# XPanel.net
KiCad netlist of a schematic drawn in EAGLE
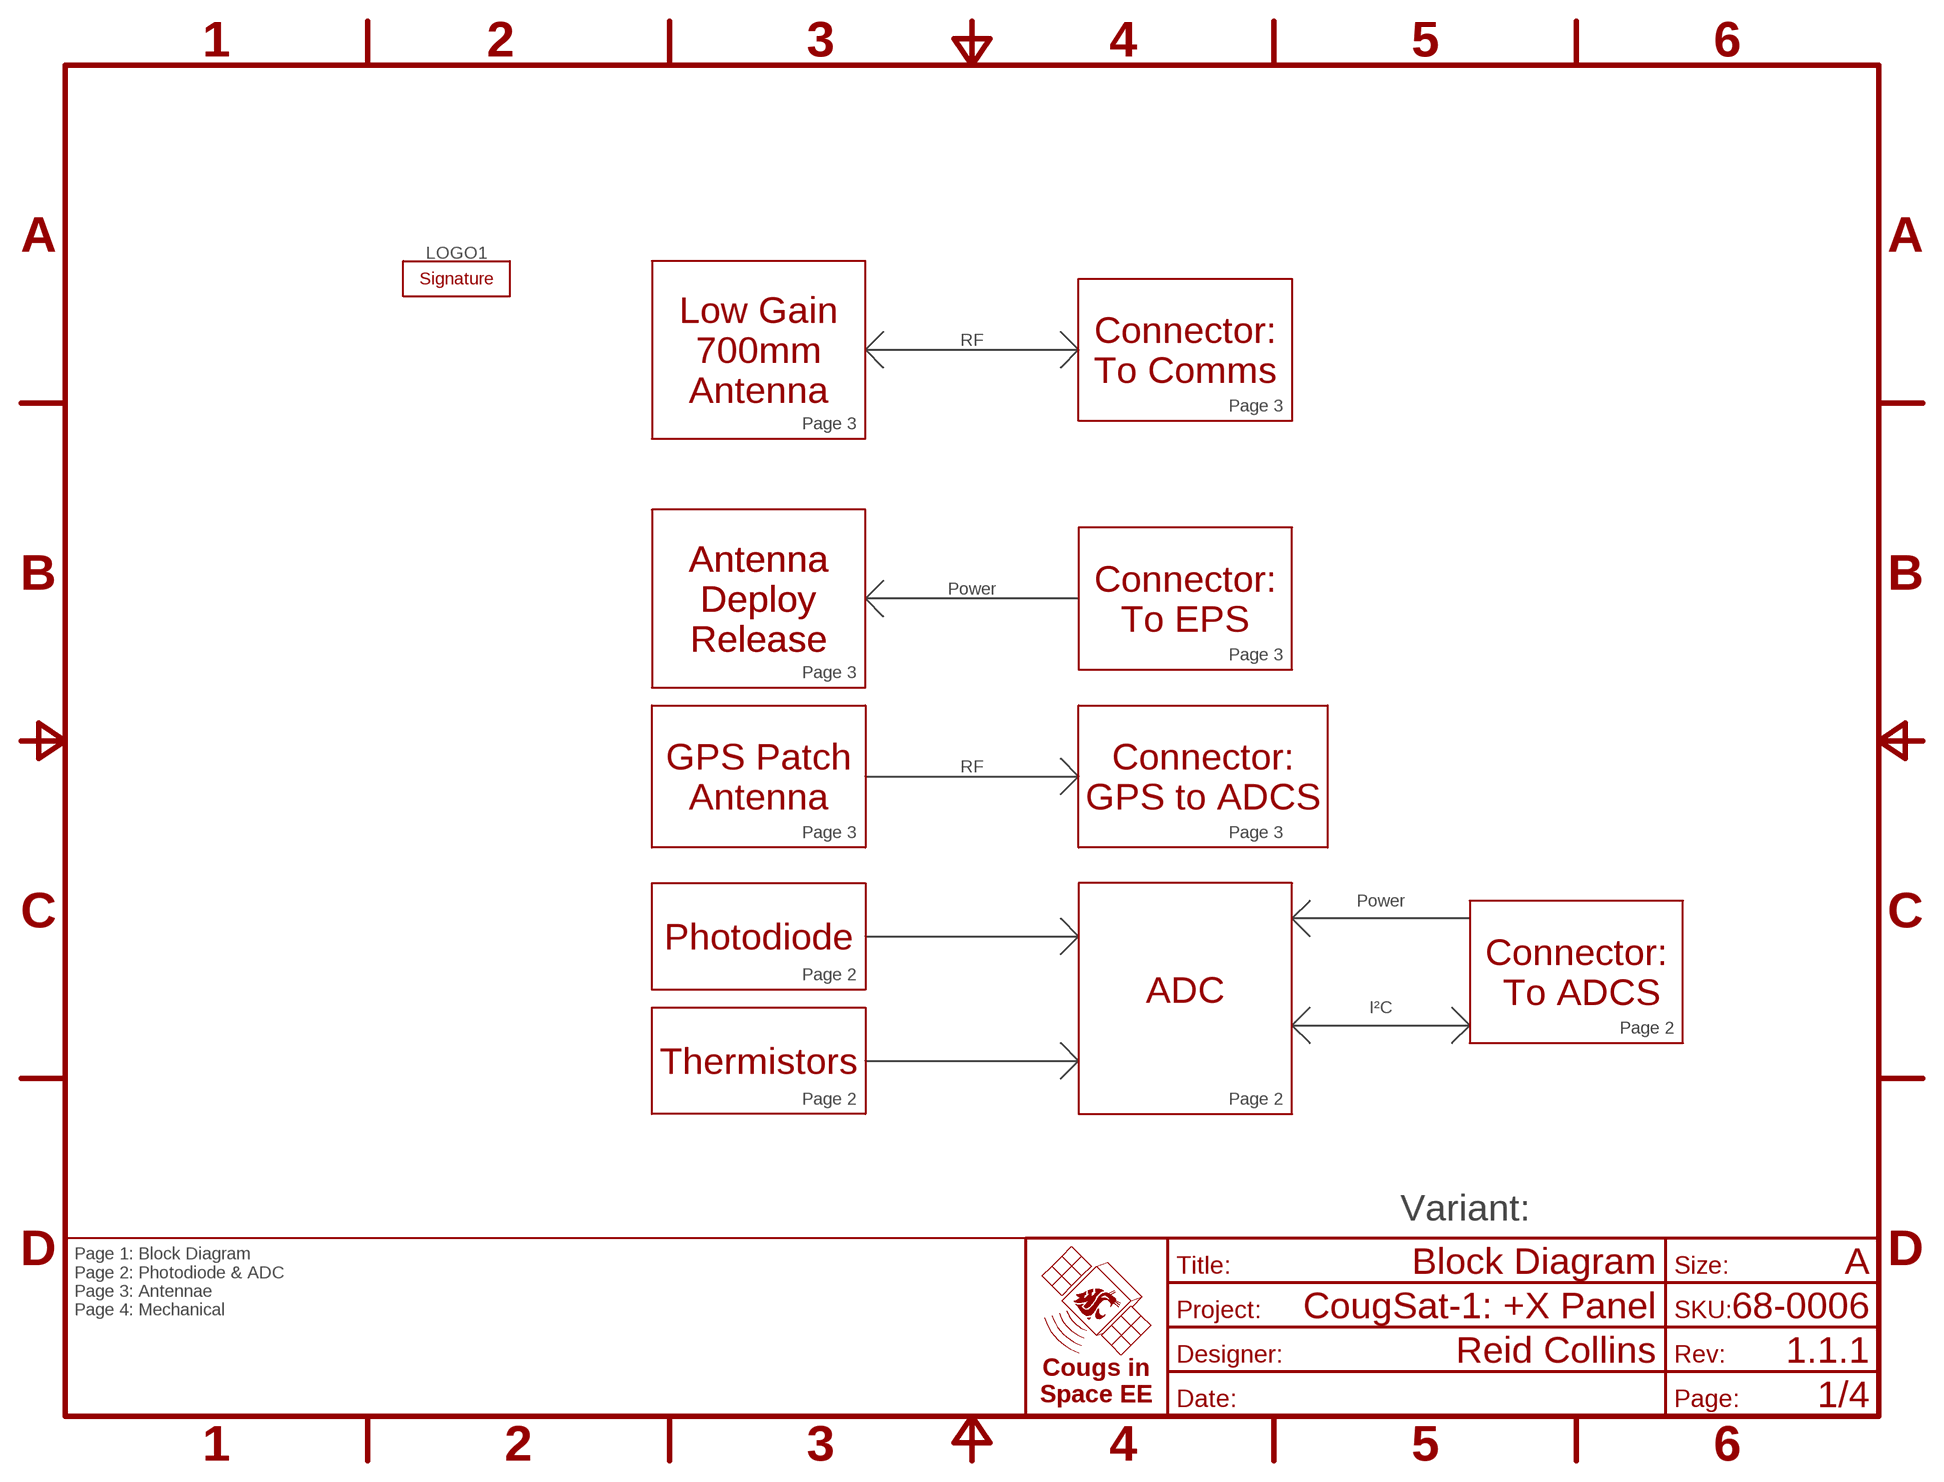
[diagram p0: schematic, sheet 1]
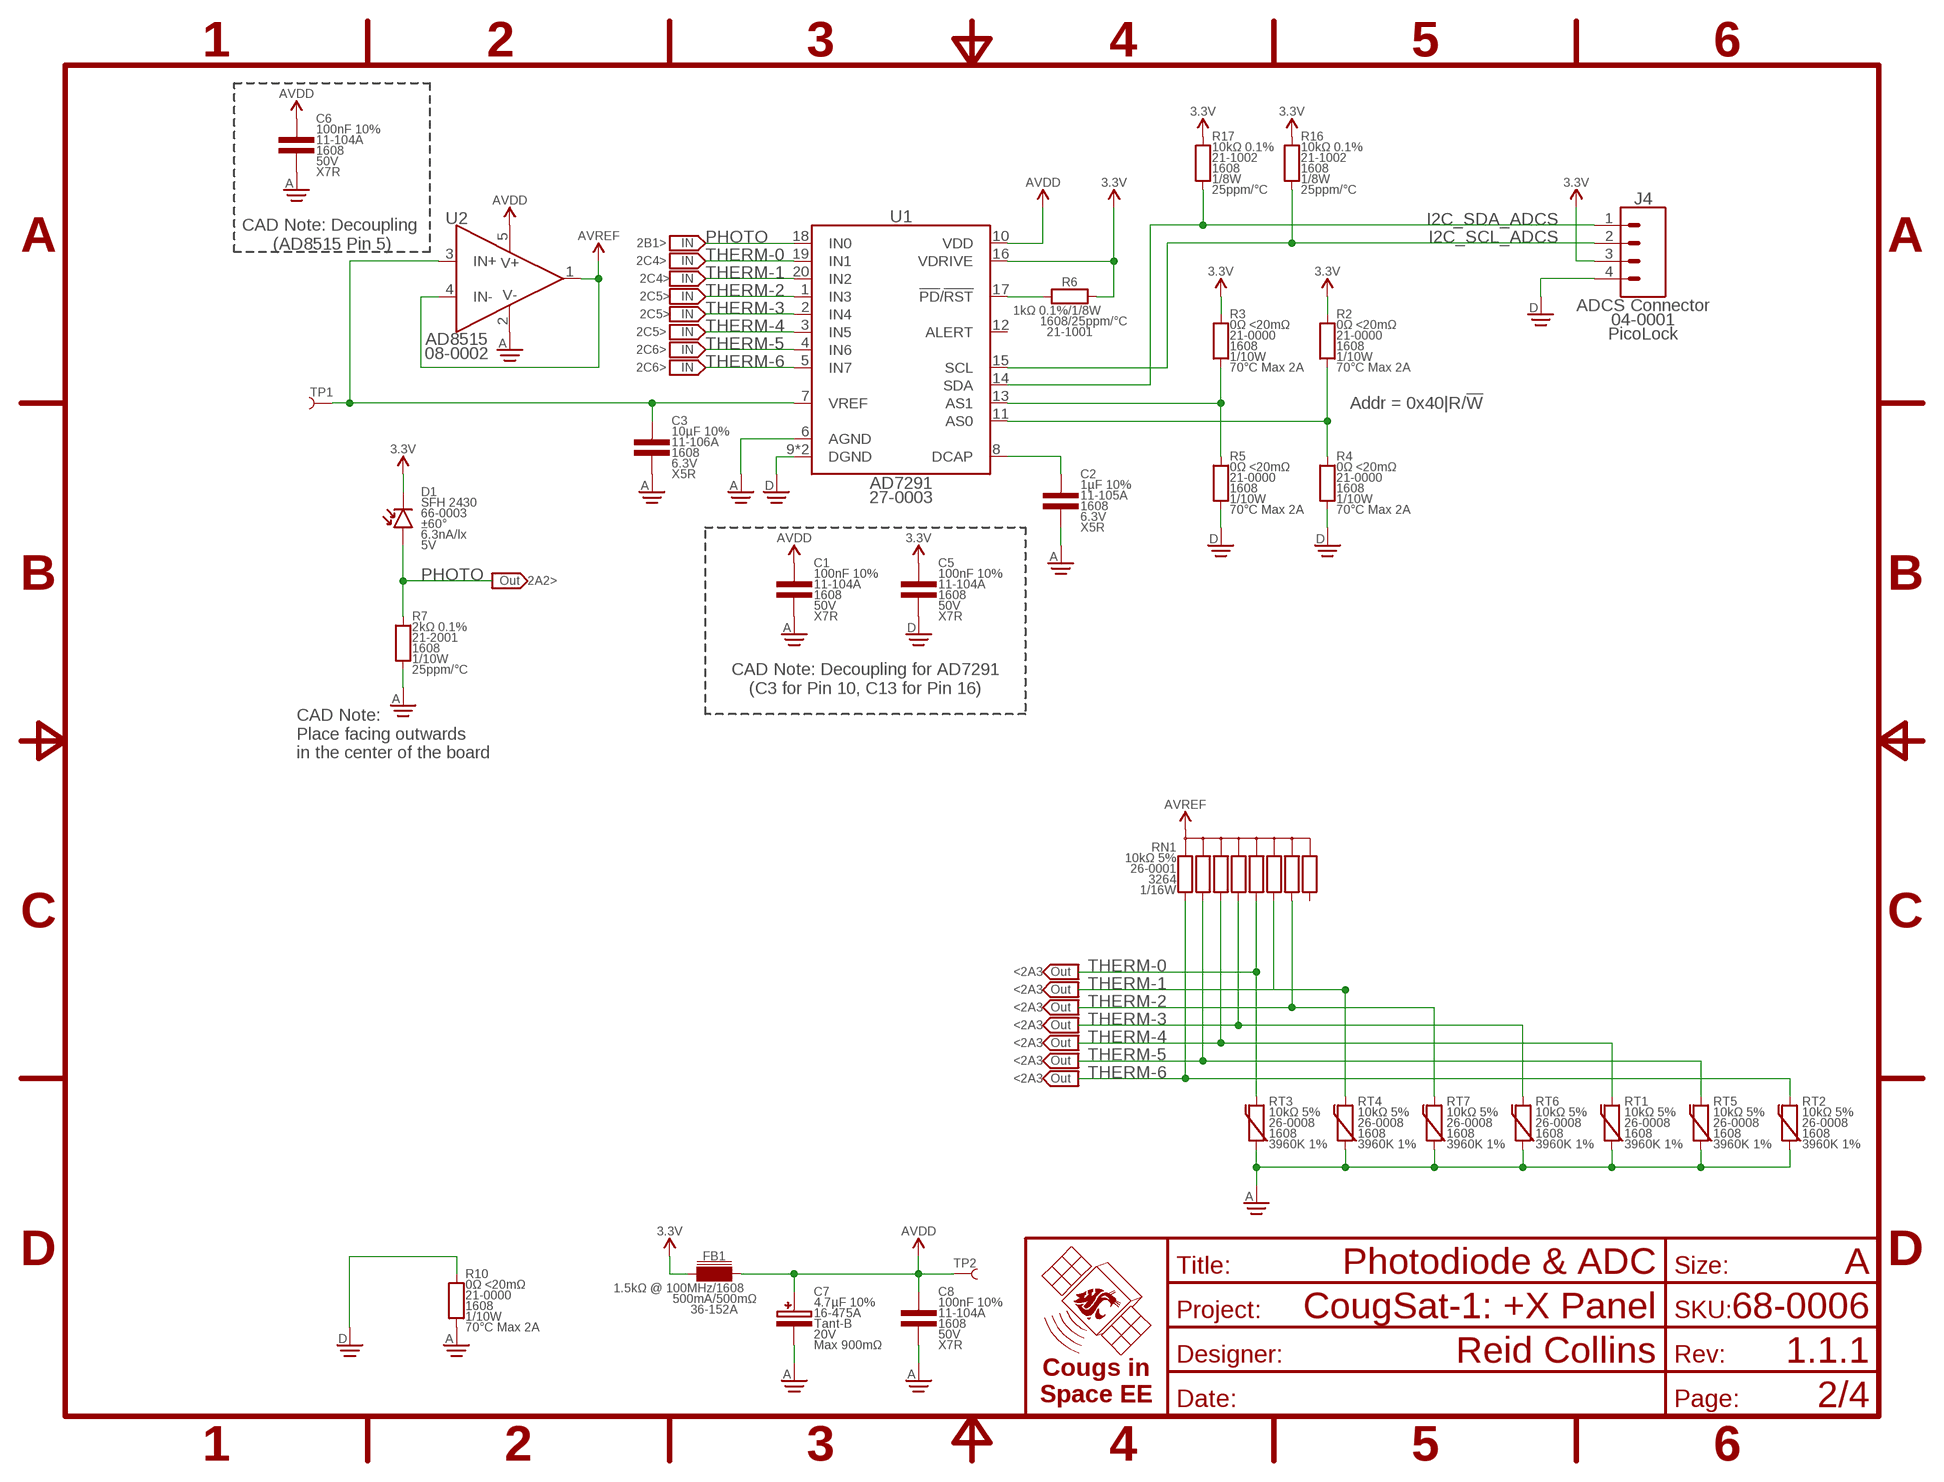
[diagram p1: schematic, sheet 2]
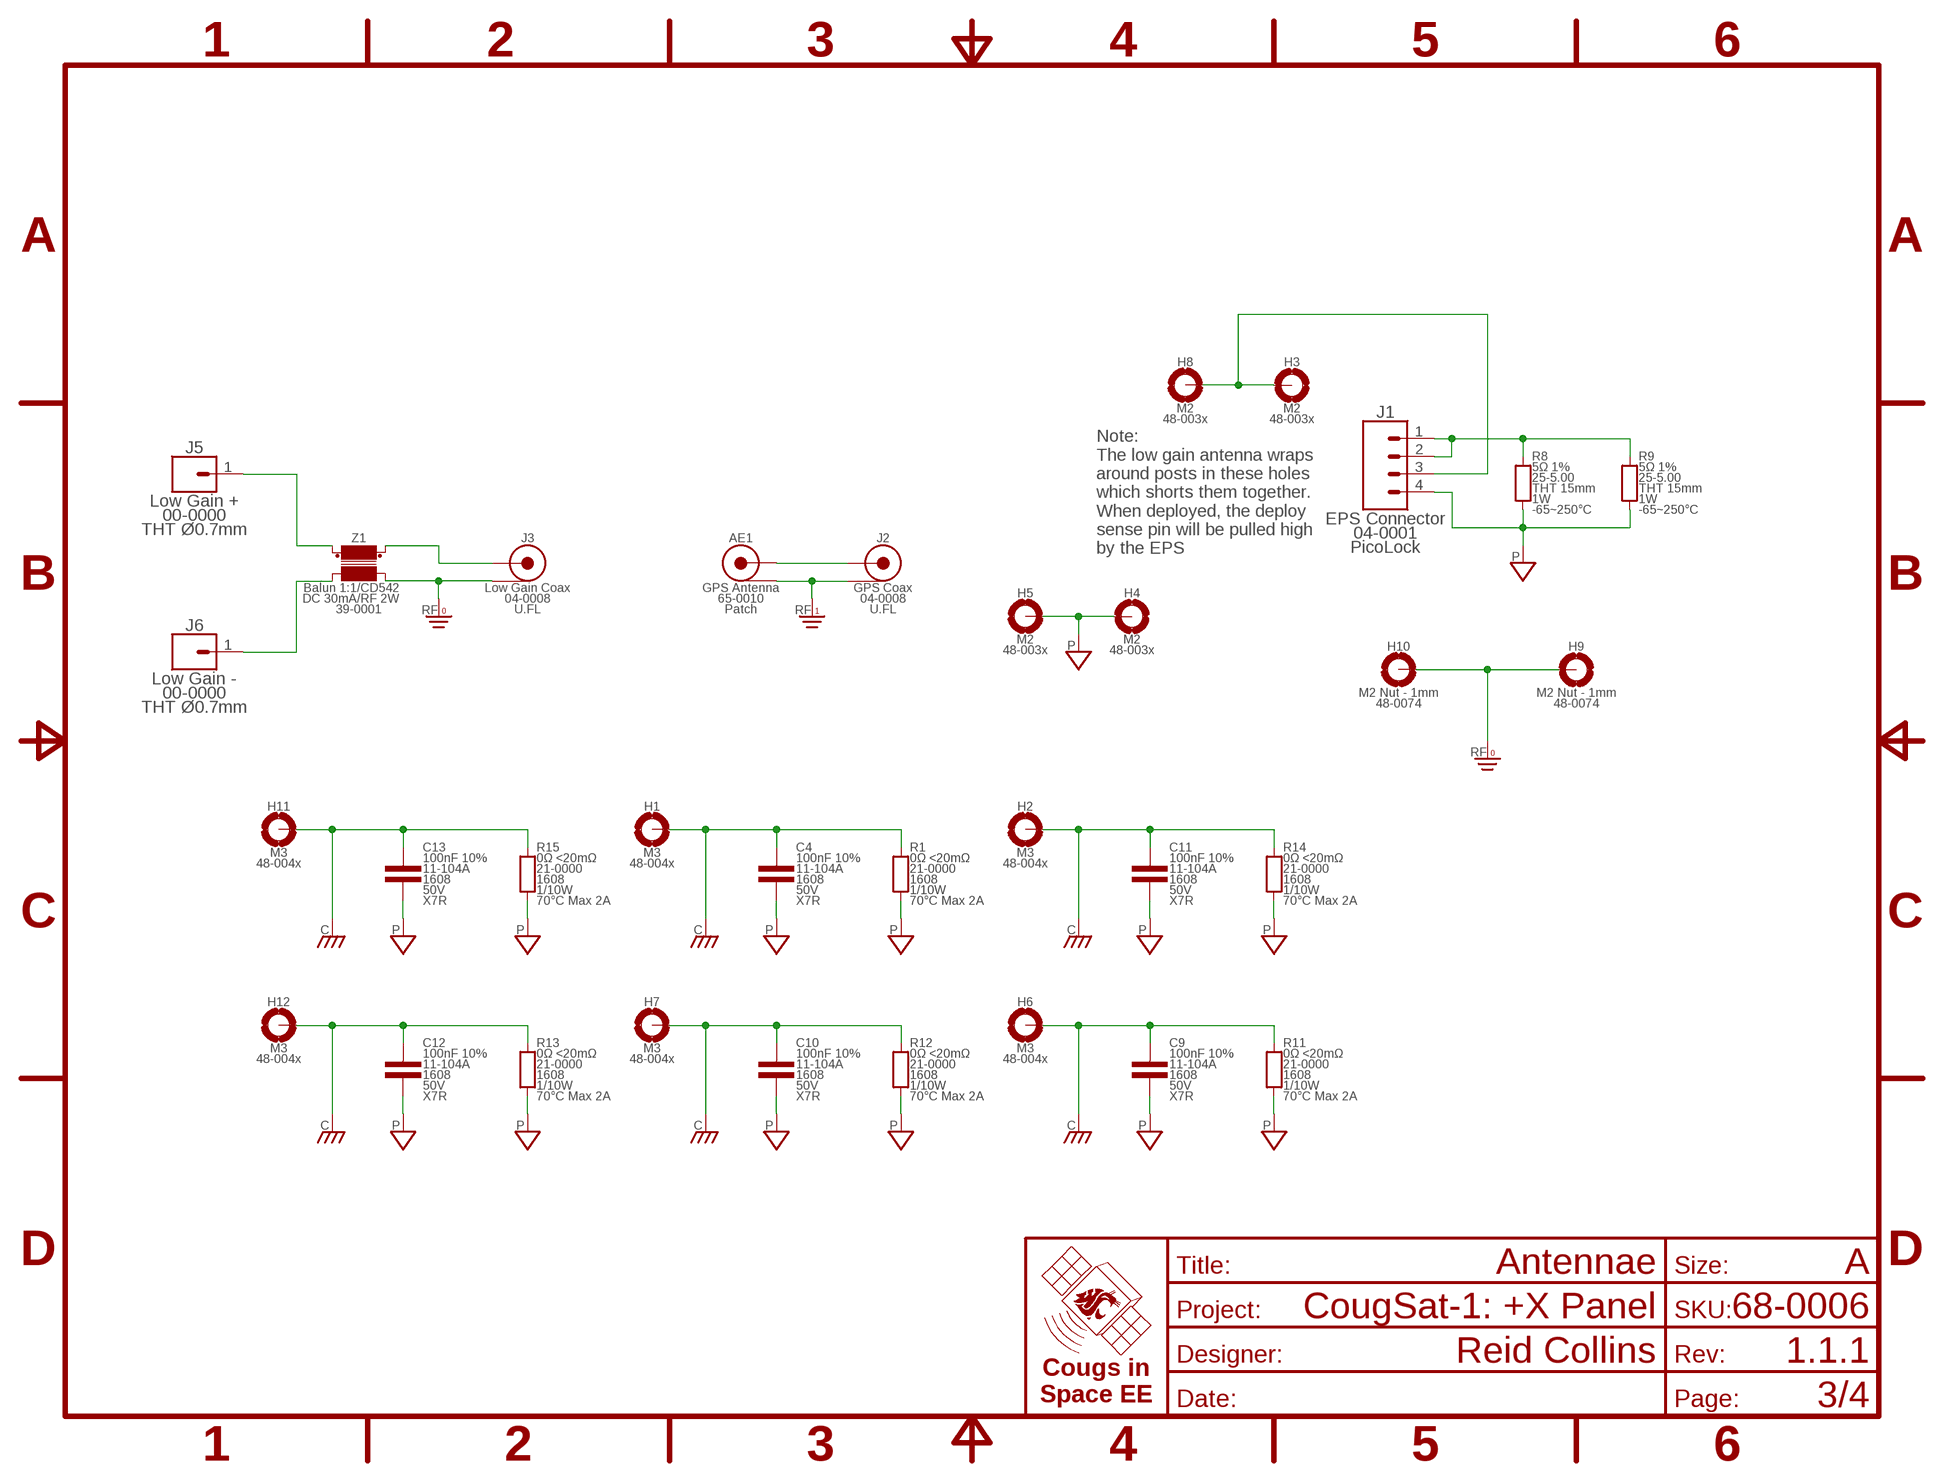
[diagram p2: schematic, sheet 3]
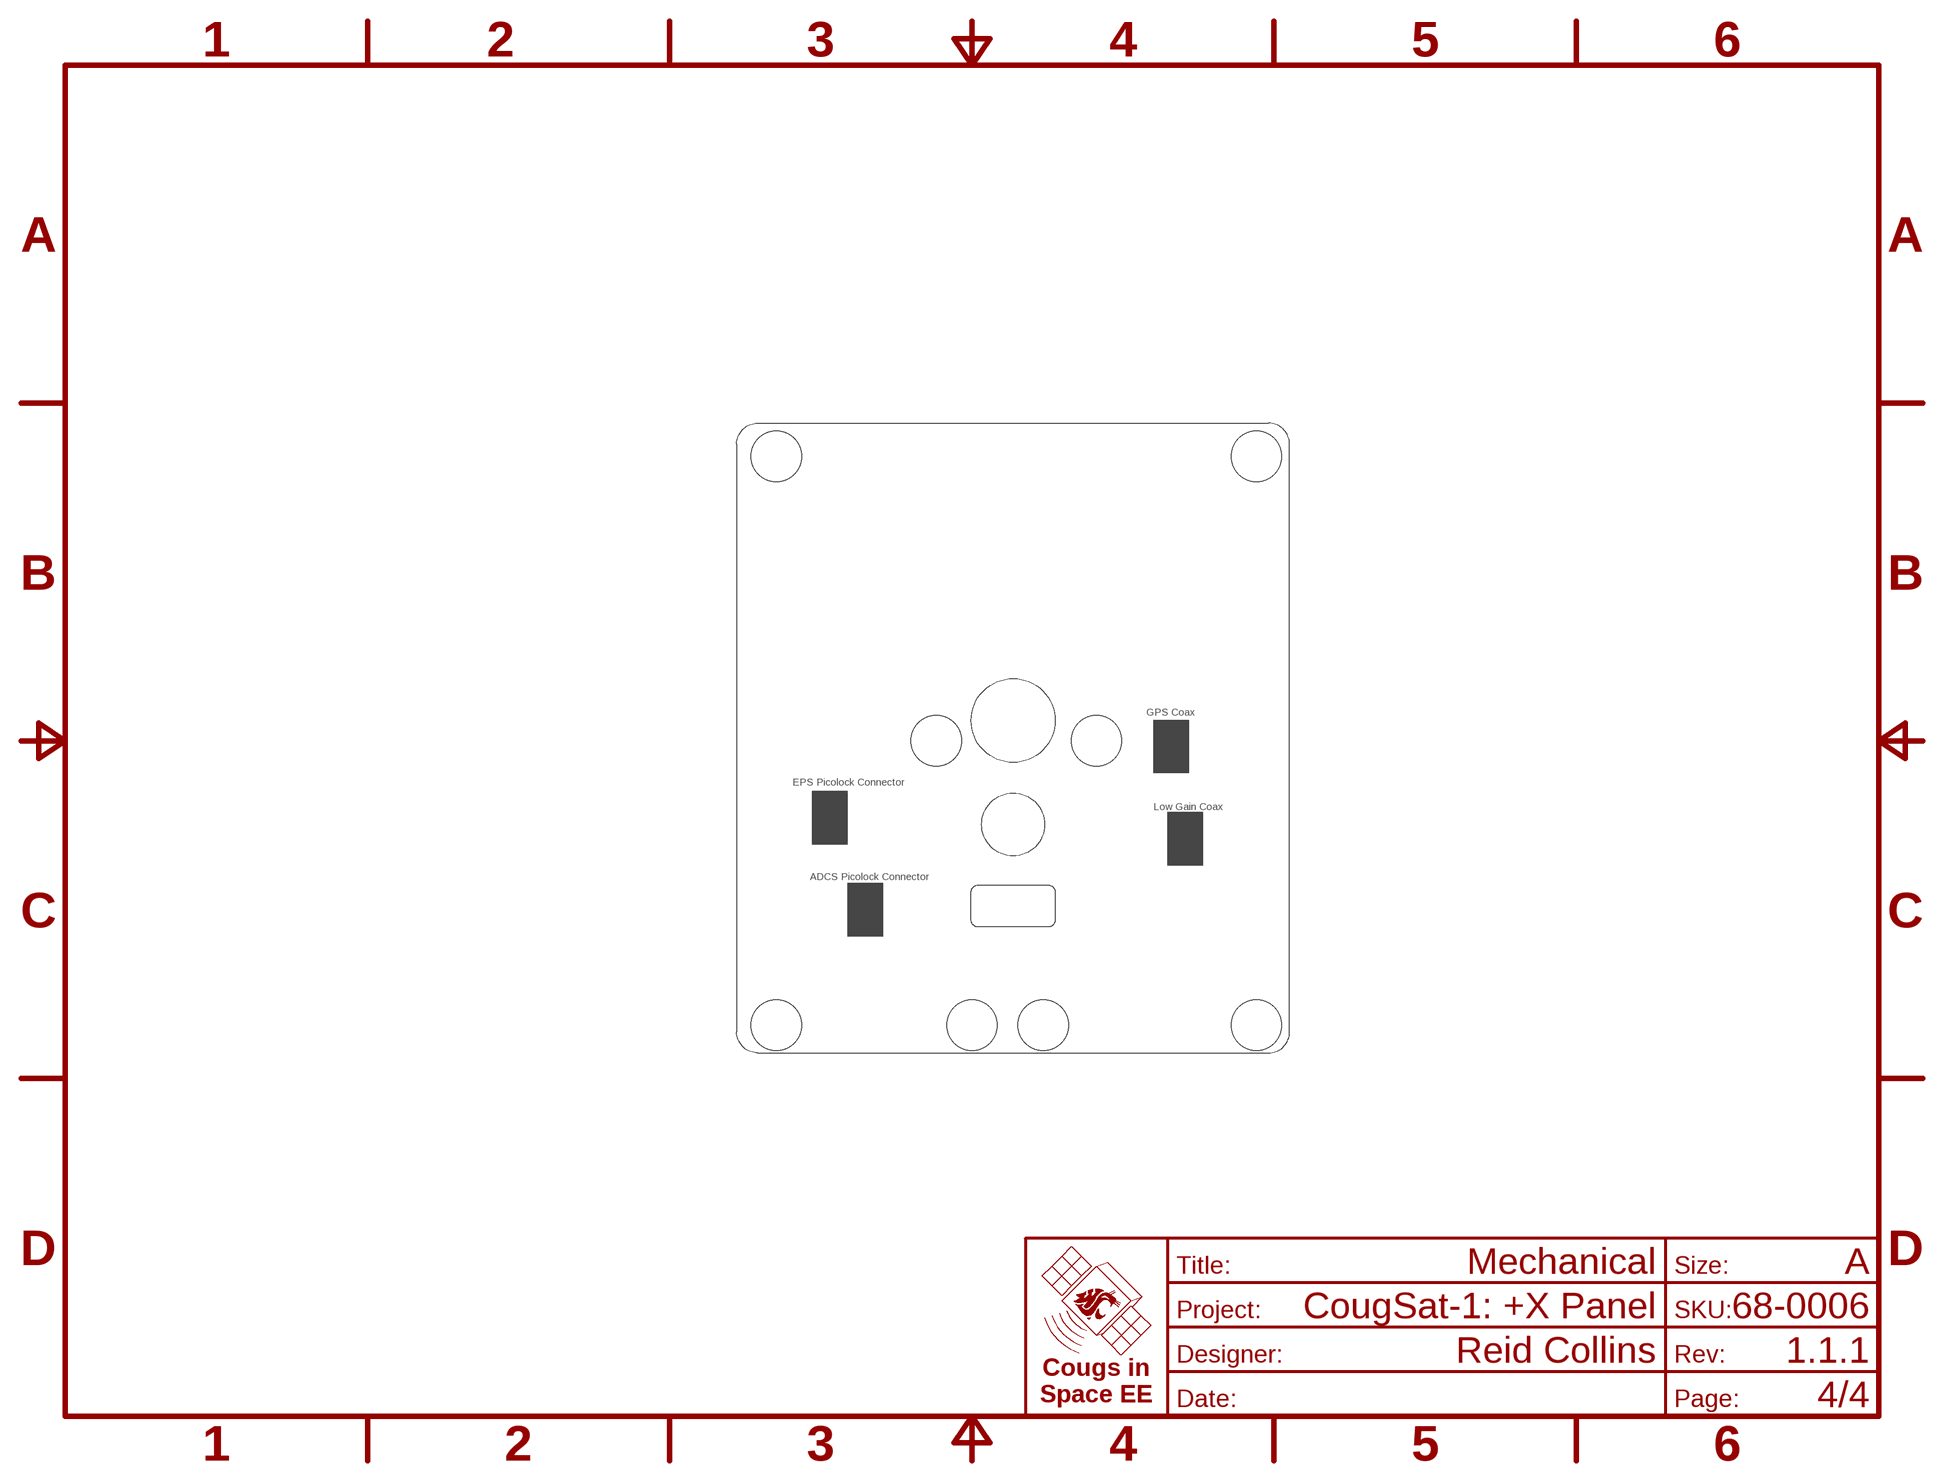
[diagram p3: schematic, sheet 4]

(export (version "E")
  (design (tool "Eeschema 10.0.6"))
  (components
    (comp (ref "C1")
      (value "100nF 10%")
      (footprint "eagle-import:1608")
      (fields
        (field (name "PACKAGE") "1608")
        (field (name "SKU") "11-104A")
        (field (name "TEMP") "X7R")
        (field (name "VOLTAGE") "50V")
      )
      (libsource (lib "eagle-import") (part "CAP-V-1608-100NF"))
    )
    (comp (ref "C2")
      (value "1µF 10%")
      (footprint "eagle-import:1608")
      (fields
        (field (name "PACKAGE") "1608")
        (field (name "SKU") "11-105A")
        (field (name "TEMP") "X5R")
        (field (name "VOLTAGE") "6.3V")
      )
      (libsource (lib "eagle-import") (part "CAP-V-1608-1UF"))
    )
    (comp (ref "C3")
      (value "10µF 10%")
      (footprint "eagle-import:1608")
      (fields
        (field (name "PACKAGE") "1608")
        (field (name "SKU") "11-106A")
        (field (name "TEMP") "X5R")
        (field (name "VOLTAGE") "6.3V")
      )
      (libsource (lib "eagle-import") (part "CAP-V-1608-10UF"))
    )
    (comp (ref "C5")
      (value "100nF 10%")
      (footprint "eagle-import:1608")
      (fields
        (field (name "PACKAGE") "1608")
        (field (name "SKU") "11-104A")
        (field (name "TEMP") "X7R")
        (field (name "VOLTAGE") "50V")
      )
      (libsource (lib "eagle-import") (part "CAP-V-1608-100NF"))
    )
    (comp (ref "C6")
      (value "100nF 10%")
      (footprint "eagle-import:1608")
      (fields
        (field (name "PACKAGE") "1608")
        (field (name "SKU") "11-104A")
        (field (name "TEMP") "X7R")
        (field (name "VOLTAGE") "50V")
      )
      (libsource (lib "eagle-import") (part "CAP-V-1608-100NF"))
    )
    (comp (ref "C7")
      (value "4.7µF 10%")
      (footprint "eagle-import:4028-POL")
      (fields
        (field (name "ESR") "Max 900mΩ")
        (field (name "PACKAGE") "Tant-B")
        (field (name "SKU") "16-475A")
        (field (name "VOLTAGE") "20V")
      )
      (libsource (lib "eagle-import") (part "CAP-POL-V-4028-4.7UF"))
    )
    (comp (ref "C8")
      (value "100nF 10%")
      (footprint "eagle-import:1608")
      (fields
        (field (name "PACKAGE") "1608")
        (field (name "SKU") "11-104A")
        (field (name "TEMP") "X7R")
        (field (name "VOLTAGE") "50V")
      )
      (libsource (lib "eagle-import") (part "CAP-V-1608-100NF"))
    )
    (comp (ref "D1")
      (value "SFH 2430")
      (footprint "eagle-import:SFH2430")
      (fields
        (field (name "SKU") "66-0003")
        (field (name "SENSITIVITY") "6.3nA/lx")
        (field (name "VR") "5V")
        (field (name "HALF_ANGLE") "±60°")
      )
      (libsource (lib "eagle-import") (part "PHOTODIODE-SFH2430"))
    )
    (comp (ref "FB1")
      (value "1.5kΩ @ 100MHz")
      (footprint "eagle-import:1608")
      (fields
        (field (name "CURRENT") "500mA")
        (field (name "DCR") "500mΩ")
        (field (name "PACKAGE") "1608")
        (field (name "SKU") "36-152A")
      )
      (libsource (lib "eagle-import") (part "CHOKE-H-1608-1.5K"))
    )
    (comp (ref "J4")
      (value "ADCS Connector")
      (footprint "eagle-import:PICOLOCK1.5-04")
      (fields (field (name "SKU") "04-0001") (field (name "PACKAGE") "PicoLock"))
      (libsource (lib "eagle-import") (part "1X04-PICOLOCK"))
    )
    (comp (ref "R2")
      (value "0Ω <20mΩ")
      (footprint "eagle-import:1608")
      (fields
        (field (name "PACKAGE") "1608")
        (field (name "POWER") "1/10W")
        (field (name "SKU") "21-0000")
        (field (name "TEMP") "70°C Max 2A")
      )
      (libsource (lib "eagle-import") (part "RES-V-1608-0"))
    )
    (comp (ref "R3")
      (value "0Ω <20mΩ")
      (footprint "eagle-import:1608")
      (fields
        (field (name "PACKAGE") "1608")
        (field (name "POWER") "1/10W")
        (field (name "SKU") "21-0000")
        (field (name "TEMP") "70°C Max 2A")
      )
      (libsource (lib "eagle-import") (part "RES-V-1608-0"))
    )
    (comp (ref "R4")
      (value "0Ω <20mΩ")
      (footprint "eagle-import:1608")
      (fields
        (field (name "PACKAGE") "1608")
        (field (name "POWER") "1/10W")
        (field (name "SKU") "21-0000")
        (field (name "TEMP") "70°C Max 2A")
      )
      (libsource (lib "eagle-import") (part "RES-V-1608-0"))
    )
    (comp (ref "R5")
      (value "0Ω <20mΩ")
      (footprint "eagle-import:1608")
      (fields
        (field (name "PACKAGE") "1608")
        (field (name "POWER") "1/10W")
        (field (name "SKU") "21-0000")
        (field (name "TEMP") "70°C Max 2A")
      )
      (libsource (lib "eagle-import") (part "RES-V-1608-0"))
    )
    (comp (ref "R6")
      (value "1kΩ 0.1%")
      (footprint "eagle-import:1608")
      (fields
        (field (name "PACKAGE") "1608")
        (field (name "POWER") "1/8W")
        (field (name "SKU") "21-1001")
        (field (name "TEMP") "25ppm/°C")
      )
      (libsource (lib "eagle-import") (part "RES-H-1608-1K"))
    )
    (comp (ref "R7")
      (value "2kΩ 0.1%")
      (footprint "eagle-import:1608")
      (fields
        (field (name "PACKAGE") "1608")
        (field (name "POWER") "1/10W")
        (field (name "SKU") "21-2001")
        (field (name "TEMP") "25ppm/°C")
      )
      (libsource (lib "eagle-import") (part "RES-V-1608-2K"))
    )
    (comp (ref "R10")
      (value "0Ω <20mΩ")
      (footprint "eagle-import:1608")
      (fields
        (field (name "PACKAGE") "1608")
        (field (name "POWER") "1/10W")
        (field (name "SKU") "21-0000")
        (field (name "TEMP") "70°C Max 2A")
      )
      (libsource (lib "eagle-import") (part "RES-V-1608-0"))
    )
    (comp (ref "R16")
      (value "10kΩ 0.1%")
      (footprint "eagle-import:1608")
      (fields
        (field (name "PACKAGE") "1608")
        (field (name "POWER") "1/8W")
        (field (name "SKU") "21-1002")
        (field (name "TEMP") "25ppm/°C")
      )
      (libsource (lib "eagle-import") (part "RES-V-1608-10K"))
    )
    (comp (ref "R17")
      (value "10kΩ 0.1%")
      (footprint "eagle-import:1608")
      (fields
        (field (name "PACKAGE") "1608")
        (field (name "POWER") "1/8W")
        (field (name "SKU") "21-1002")
        (field (name "TEMP") "25ppm/°C")
      )
      (libsource (lib "eagle-import") (part "RES-V-1608-10K"))
    )
    (comp (ref "RN1")
      (value "10kΩ 5%")
      (footprint "eagle-import:3264")
      (fields (field (name "PACKAGE") "3264") (field (name "POWER") "1/16W") (field (name "SKU") "26-0001"))
      (libsource (lib "eagle-import") (part "RES_BUS-10-3264-10K"))
    )
    (comp (ref "RT1")
      (value "10kΩ 5%")
      (footprint "eagle-import:1608")
      (fields
        (field (name "B2585") "3960K 1%")
        (field (name "PACKAGE") "1608")
        (field (name "SKU") "26-0008")
      )
      (libsource (lib "eagle-import") (part "THERMISTOR-V-1608-10K"))
    )
    (comp (ref "RT2")
      (value "10kΩ 5%")
      (footprint "eagle-import:1608")
      (fields
        (field (name "B2585") "3960K 1%")
        (field (name "PACKAGE") "1608")
        (field (name "SKU") "26-0008")
      )
      (libsource (lib "eagle-import") (part "THERMISTOR-V-1608-10K"))
    )
    (comp (ref "RT3")
      (value "10kΩ 5%")
      (footprint "eagle-import:1608")
      (fields
        (field (name "B2585") "3960K 1%")
        (field (name "PACKAGE") "1608")
        (field (name "SKU") "26-0008")
      )
      (libsource (lib "eagle-import") (part "THERMISTOR-V-1608-10K"))
    )
    (comp (ref "RT4")
      (value "10kΩ 5%")
      (footprint "eagle-import:1608")
      (fields
        (field (name "B2585") "3960K 1%")
        (field (name "PACKAGE") "1608")
        (field (name "SKU") "26-0008")
      )
      (libsource (lib "eagle-import") (part "THERMISTOR-V-1608-10K"))
    )
    (comp (ref "RT5")
      (value "10kΩ 5%")
      (footprint "eagle-import:1608")
      (fields
        (field (name "B2585") "3960K 1%")
        (field (name "PACKAGE") "1608")
        (field (name "SKU") "26-0008")
      )
      (libsource (lib "eagle-import") (part "THERMISTOR-V-1608-10K"))
    )
    (comp (ref "RT6")
      (value "10kΩ 5%")
      (footprint "eagle-import:1608")
      (fields
        (field (name "B2585") "3960K 1%")
        (field (name "PACKAGE") "1608")
        (field (name "SKU") "26-0008")
      )
      (libsource (lib "eagle-import") (part "THERMISTOR-V-1608-10K"))
    )
    (comp (ref "RT7")
      (value "10kΩ 5%")
      (footprint "eagle-import:1608")
      (fields
        (field (name "B2585") "3960K 1%")
        (field (name "PACKAGE") "1608")
        (field (name "SKU") "26-0008")
      )
      (libsource (lib "eagle-import") (part "THERMISTOR-V-1608-10K"))
    )
    (comp (ref "TP1")
      (value "TEST_POINT-SMD-C-1.25")
      (footprint "eagle-import:SMD-C-1.25")
      (libsource (lib "eagle-import") (part "TEST_POINT-SMD-C-1.25"))
    )
    (comp (ref "TP2")
      (value "TEST_POINT-SMD-C-1.25")
      (footprint "eagle-import:SMD-C-1.25")
      (libsource (lib "eagle-import") (part "TEST_POINT-SMD-C-1.25"))
    )
    (comp (ref "U1")
      (value "AD7291")
      (footprint "eagle-import:QFN-20-4040")
      (fields (field (name "SKU") "27-0003"))
      (libsource (lib "eagle-import") (part "AD7291"))
    )
    (comp (ref "U2")
      (value "AD8515")
      (footprint "eagle-import:SOT23-5")
      (fields (field (name "SKU") "08-0002"))
      (libsource (lib "eagle-import") (part "OPAMP-1-AD8515"))
    )
    (comp (ref "AE1")
      (value "GPS Antenna")
      (footprint "eagle-import:ANTENNA-GPS")
      (fields (field (name "SKU") "65-0010") (field (name "PACKAGE") "Patch"))
      (libsource (lib "eagle-import") (part "ANTENNA-GPSPATCH"))
    )
    (comp (ref "C4")
      (value "100nF 10%")
      (footprint "eagle-import:1608")
      (fields
        (field (name "PACKAGE") "1608")
        (field (name "SKU") "11-104A")
        (field (name "TEMP") "X7R")
        (field (name "VOLTAGE") "50V")
      )
      (libsource (lib "eagle-import") (part "CAP-V-1608-100NF"))
    )
    (comp (ref "C9")
      (value "100nF 10%")
      (footprint "eagle-import:1608")
      (fields
        (field (name "PACKAGE") "1608")
        (field (name "SKU") "11-104A")
        (field (name "TEMP") "X7R")
        (field (name "VOLTAGE") "50V")
      )
      (libsource (lib "eagle-import") (part "CAP-V-1608-100NF"))
    )
    (comp (ref "C10")
      (value "100nF 10%")
      (footprint "eagle-import:1608")
      (fields
        (field (name "PACKAGE") "1608")
        (field (name "SKU") "11-104A")
        (field (name "TEMP") "X7R")
        (field (name "VOLTAGE") "50V")
      )
      (libsource (lib "eagle-import") (part "CAP-V-1608-100NF"))
    )
    (comp (ref "C11")
      (value "100nF 10%")
      (footprint "eagle-import:1608")
      (fields
        (field (name "PACKAGE") "1608")
        (field (name "SKU") "11-104A")
        (field (name "TEMP") "X7R")
        (field (name "VOLTAGE") "50V")
      )
      (libsource (lib "eagle-import") (part "CAP-V-1608-100NF"))
    )
    (comp (ref "C12")
      (value "100nF 10%")
      (footprint "eagle-import:1608")
      (fields
        (field (name "PACKAGE") "1608")
        (field (name "SKU") "11-104A")
        (field (name "TEMP") "X7R")
        (field (name "VOLTAGE") "50V")
      )
      (libsource (lib "eagle-import") (part "CAP-V-1608-100NF"))
    )
    (comp (ref "C13")
      (value "100nF 10%")
      (footprint "eagle-import:1608")
      (fields
        (field (name "PACKAGE") "1608")
        (field (name "SKU") "11-104A")
        (field (name "TEMP") "X7R")
        (field (name "VOLTAGE") "50V")
      )
      (libsource (lib "eagle-import") (part "CAP-V-1608-100NF"))
    )
    (comp (ref "H1")
      (value "M3")
      (footprint "eagle-import:MOUNTING_HOLE-3.3")
      (fields (field (name "SKU") "48-004x"))
      (libsource (lib "eagle-import") (part "MOUNTING_HOLE-3.3"))
    )
    (comp (ref "H2")
      (value "M3")
      (footprint "eagle-import:MOUNTING_HOLE-3.3")
      (fields (field (name "SKU") "48-004x"))
      (libsource (lib "eagle-import") (part "MOUNTING_HOLE-3.3"))
    )
    (comp (ref "H3")
      (value "M2")
      (footprint "eagle-import:MOUNTING_HOLE-2.2")
      (fields (field (name "SKU") "48-003x"))
      (libsource (lib "eagle-import") (part "MOUNTING_HOLE-2.2"))
    )
    (comp (ref "H4")
      (value "M2")
      (footprint "eagle-import:MOUNTING_HOLE-2.2")
      (fields (field (name "SKU") "48-003x"))
      (libsource (lib "eagle-import") (part "MOUNTING_HOLE-2.2"))
    )
    (comp (ref "H5")
      (value "M2")
      (footprint "eagle-import:MOUNTING_HOLE-2.2")
      (fields (field (name "SKU") "48-003x"))
      (libsource (lib "eagle-import") (part "MOUNTING_HOLE-2.2"))
    )
    (comp (ref "H6")
      (value "M3")
      (footprint "eagle-import:MOUNTING_HOLE-3.3")
      (fields (field (name "SKU") "48-004x"))
      (libsource (lib "eagle-import") (part "MOUNTING_HOLE-3.3"))
    )
    (comp (ref "H7")
      (value "M3")
      (footprint "eagle-import:MOUNTING_HOLE-3.3")
      (fields (field (name "SKU") "48-004x"))
      (libsource (lib "eagle-import") (part "MOUNTING_HOLE-3.3"))
    )
    (comp (ref "H8")
      (value "M2")
      (footprint "eagle-import:MOUNTING_HOLE-2.2")
      (fields (field (name "SKU") "48-003x"))
      (libsource (lib "eagle-import") (part "MOUNTING_HOLE-2.2"))
    )
    (comp (ref "H9")
      (value "M2 Nut - 1mm")
      (footprint "eagle-import:MOUNTING_HOLE-M2_NUT")
      (fields (field (name "SKU") "48-0074"))
      (libsource (lib "eagle-import") (part "MOUNTING_HOLE-M2_NUT-1MM"))
    )
    (comp (ref "H10")
      (value "M2 Nut - 1mm")
      (footprint "eagle-import:MOUNTING_HOLE-M2_NUT")
      (fields (field (name "SKU") "48-0074"))
      (libsource (lib "eagle-import") (part "MOUNTING_HOLE-M2_NUT-1MM"))
    )
    (comp (ref "H11")
      (value "M3")
      (footprint "eagle-import:MOUNTING_HOLE-3.3")
      (fields (field (name "SKU") "48-004x"))
      (libsource (lib "eagle-import") (part "MOUNTING_HOLE-3.3"))
    )
    (comp (ref "H12")
      (value "M3")
      (footprint "eagle-import:MOUNTING_HOLE-3.3")
      (fields (field (name "SKU") "48-004x"))
      (libsource (lib "eagle-import") (part "MOUNTING_HOLE-3.3"))
    )
    (comp (ref "J1")
      (value "EPS Connector")
      (footprint "eagle-import:PICOLOCK1.5-04")
      (fields (field (name "SKU") "04-0001") (field (name "PACKAGE") "PicoLock"))
      (libsource (lib "eagle-import") (part "1X04-PICOLOCK"))
    )
    (comp (ref "J2")
      (value "GPS Coax")
      (footprint "eagle-import:U.FL")
      (fields (field (name "SKU") "04-0008") (field (name "PACKAGE") "U.FL"))
      (libsource (lib "eagle-import") (part "COAX-U.FL"))
    )
    (comp (ref "J3")
      (value "Low Gain Coax")
      (footprint "eagle-import:U.FL")
      (fields (field (name "SKU") "04-0008") (field (name "PACKAGE") "U.FL"))
      (libsource (lib "eagle-import") (part "COAX-U.FL"))
    )
    (comp (ref "J5")
      (value "Low Gain +")
      (footprint "eagle-import:THT-0.7")
      (fields (field (name "SKU") "00-0000") (field (name "PACKAGE") "THT Ø0.7mm"))
      (libsource (lib "eagle-import") (part "1X01-THT-0.7"))
    )
    (comp (ref "J6")
      (value "Low Gain -")
      (footprint "eagle-import:THT-0.7")
      (fields (field (name "SKU") "00-0000") (field (name "PACKAGE") "THT Ø0.7mm"))
      (libsource (lib "eagle-import") (part "1X01-THT-0.7"))
    )
    (comp (ref "R1")
      (value "0Ω <20mΩ")
      (footprint "eagle-import:1608")
      (fields
        (field (name "PACKAGE") "1608")
        (field (name "POWER") "1/10W")
        (field (name "SKU") "21-0000")
        (field (name "TEMP") "70°C Max 2A")
      )
      (libsource (lib "eagle-import") (part "RES-V-1608-0"))
    )
    (comp (ref "R8")
      (value "5Ω 1%")
      (footprint "eagle-import:THT-15MM")
      (fields
        (field (name "PACKAGE") "THT 15mm")
        (field (name "POWER") "1W")
        (field (name "SKU") "25-5.00")
        (field (name "TEMP") "-65~250°C")
      )
      (libsource (lib "eagle-import") (part "RES-V-THT-15MM-5R"))
    )
    (comp (ref "R9")
      (value "5Ω 1%")
      (footprint "eagle-import:THT-15MM")
      (fields
        (field (name "PACKAGE") "THT 15mm")
        (field (name "POWER") "1W")
        (field (name "SKU") "25-5.00")
        (field (name "TEMP") "-65~250°C")
      )
      (libsource (lib "eagle-import") (part "RES-V-THT-15MM-5R"))
    )
    (comp (ref "R11")
      (value "0Ω <20mΩ")
      (footprint "eagle-import:1608")
      (fields
        (field (name "PACKAGE") "1608")
        (field (name "POWER") "1/10W")
        (field (name "SKU") "21-0000")
        (field (name "TEMP") "70°C Max 2A")
      )
      (libsource (lib "eagle-import") (part "RES-V-1608-0"))
    )
    (comp (ref "R12")
      (value "0Ω <20mΩ")
      (footprint "eagle-import:1608")
      (fields
        (field (name "PACKAGE") "1608")
        (field (name "POWER") "1/10W")
        (field (name "SKU") "21-0000")
        (field (name "TEMP") "70°C Max 2A")
      )
      (libsource (lib "eagle-import") (part "RES-V-1608-0"))
    )
    (comp (ref "R13")
      (value "0Ω <20mΩ")
      (footprint "eagle-import:1608")
      (fields
        (field (name "PACKAGE") "1608")
        (field (name "POWER") "1/10W")
        (field (name "SKU") "21-0000")
        (field (name "TEMP") "70°C Max 2A")
      )
      (libsource (lib "eagle-import") (part "RES-V-1608-0"))
    )
    (comp (ref "R14")
      (value "0Ω <20mΩ")
      (footprint "eagle-import:1608")
      (fields
        (field (name "PACKAGE") "1608")
        (field (name "POWER") "1/10W")
        (field (name "SKU") "21-0000")
        (field (name "TEMP") "70°C Max 2A")
      )
      (libsource (lib "eagle-import") (part "RES-V-1608-0"))
    )
    (comp (ref "R15")
      (value "0Ω <20mΩ")
      (footprint "eagle-import:1608")
      (fields
        (field (name "PACKAGE") "1608")
        (field (name "POWER") "1/10W")
        (field (name "SKU") "21-0000")
        (field (name "TEMP") "70°C Max 2A")
      )
      (libsource (lib "eagle-import") (part "RES-V-1608-0"))
    )
    (comp (ref "Z1")
      (value "Balun 1:1")
      (footprint "eagle-import:CD542")
      (fields
        (field (name "CURRENT") "DC 30mA")
        (field (name "PACKAGE") "CD542")
        (field (name "POWER") "RF 2W")
        (field (name "SKU") "39-0001")
      )
      (libsource (lib "eagle-import") (part "BALUN-CD542-ADTL1-12+"))
    )
    (comp (ref "LOGO1")
      (value "SIGNATUREJAYSON")
      (footprint "eagle-import:SIGN-JAYSON")
      (libsource (lib "eagle-import") (part "SIGNATUREJAYSON"))
    )
  )
  (nets
    (net (code "1") (name "3.3V") (class "Default")
      (node (ref "C5") (pin "1") (pinfunction "1_1") (pintype "passive"))
      (node (ref "D1") (pin "C") (pinfunction "C_C") (pintype "passive"))
      (node (ref "FB1") (pin "1") (pinfunction "1_1") (pintype "passive"))
      (node (ref "J4") (pin "3") (pinfunction "3_3") (pintype "passive"))
      (node (ref "R16") (pin "2") (pinfunction "2_2") (pintype "passive"))
      (node (ref "R17") (pin "2") (pinfunction "2_2") (pintype "passive"))
      (node (ref "R2") (pin "2") (pinfunction "2_2") (pintype "passive"))
      (node (ref "R3") (pin "2") (pinfunction "2_2") (pintype "passive"))
      (node (ref "R6") (pin "2") (pinfunction "2_2") (pintype "passive"))
      (node (ref "U1") (pin "16") (pinfunction "VDRIVE_16") (pintype "power_in"))
    )
    (net (code "2") (name "AGND") (class "Default")
      (node (ref "C1") (pin "2") (pinfunction "2_2") (pintype "passive"))
      (node (ref "C2") (pin "2") (pinfunction "2_2") (pintype "passive"))
      (node (ref "C3") (pin "2") (pinfunction "2_2") (pintype "passive"))
      (node (ref "C6") (pin "2") (pinfunction "2_2") (pintype "passive"))
      (node (ref "C7") (pin "C") (pinfunction "C_C") (pintype "passive"))
      (node (ref "C8") (pin "2") (pinfunction "2_2") (pintype "passive"))
      (node (ref "R10") (pin "1") (pinfunction "1_1") (pintype "passive"))
      (node (ref "R7") (pin "1") (pinfunction "1_1") (pintype "passive"))
      (node (ref "RT1") (pin "1") (pinfunction "1_1") (pintype "passive"))
      (node (ref "RT2") (pin "1") (pinfunction "1_1") (pintype "passive"))
      (node (ref "RT3") (pin "1") (pinfunction "1_1") (pintype "passive"))
      (node (ref "RT4") (pin "1") (pinfunction "1_1") (pintype "passive"))
      (node (ref "RT5") (pin "1") (pinfunction "1_1") (pintype "passive"))
      (node (ref "RT6") (pin "1") (pinfunction "1_1") (pintype "passive"))
      (node (ref "RT7") (pin "1") (pinfunction "1_1") (pintype "passive"))
      (node (ref "U1") (pin "6") (pinfunction "AGND_6") (pintype "power_in"))
      (node (ref "U2") (pin "2") (pinfunction "V-_2") (pintype "power_in"))
    )
    (net (code "3") (name "AVDD") (class "Default")
      (node (ref "C1") (pin "1") (pinfunction "1_1") (pintype "passive"))
      (node (ref "C6") (pin "1") (pinfunction "1_1") (pintype "passive"))
      (node (ref "C7") (pin "A") (pinfunction "A_A") (pintype "passive"))
      (node (ref "C8") (pin "1") (pinfunction "1_1") (pintype "passive"))
      (node (ref "FB1") (pin "2") (pinfunction "2_2") (pintype "passive"))
      (node (ref "TP2") (pin "1") (pinfunction "1_1") (pintype "passive"))
      (node (ref "U1") (pin "10") (pinfunction "VDD_10") (pintype "power_in"))
      (node (ref "U2") (pin "5") (pinfunction "V+_5") (pintype "power_in"))
    )
    (net (code "4") (name "AVREF") (class "Default")
      (node (ref "RN1") (pin "10") (pinfunction "C_10") (pintype "passive"))
      (node (ref "RN1") (pin "5") (pinfunction "C_5") (pintype "passive"))
      (node (ref "U2") (pin "1") (pinfunction "OUT_1") (pintype "output"))
      (node (ref "U2") (pin "4") (pinfunction "IN-_4") (pintype "passive"))
    )
    (net (code "5") (name "CHASSIS") (class "Default")
      (node (ref "C10") (pin "1") (pinfunction "1_1") (pintype "passive"))
      (node (ref "C11") (pin "1") (pinfunction "1_1") (pintype "passive"))
      (node (ref "C12") (pin "1") (pinfunction "1_1") (pintype "passive"))
      (node (ref "C13") (pin "1") (pinfunction "1_1") (pintype "passive"))
      (node (ref "C4") (pin "1") (pinfunction "1_1") (pintype "passive"))
      (node (ref "C9") (pin "1") (pinfunction "1_1") (pintype "passive"))
      (node (ref "H1") (pin "1") (pinfunction "MOUNT_1") (pintype "passive"))
      (node (ref "H1") (pin "V1") (pinfunction "MOUNT_V1") (pintype "passive"))
      (node (ref "H1") (pin "V10") (pinfunction "MOUNT_V10") (pintype "passive"))
      (node (ref "H1") (pin "V2") (pinfunction "MOUNT_V2") (pintype "passive"))
      (node (ref "H1") (pin "V3") (pinfunction "MOUNT_V3") (pintype "passive"))
      (node (ref "H1") (pin "V4") (pinfunction "MOUNT_V4") (pintype "passive"))
      (node (ref "H1") (pin "V5") (pinfunction "MOUNT_V5") (pintype "passive"))
      (node (ref "H1") (pin "V6") (pinfunction "MOUNT_V6") (pintype "passive"))
      (node (ref "H1") (pin "V7") (pinfunction "MOUNT_V7") (pintype "passive"))
      (node (ref "H1") (pin "V8") (pinfunction "MOUNT_V8") (pintype "passive"))
      (node (ref "H1") (pin "V9") (pinfunction "MOUNT_V9") (pintype "passive"))
      (node (ref "H11") (pin "1") (pinfunction "MOUNT_1") (pintype "passive"))
      (node (ref "H11") (pin "V1") (pinfunction "MOUNT_V1") (pintype "passive"))
      (node (ref "H11") (pin "V10") (pinfunction "MOUNT_V10") (pintype "passive"))
      (node (ref "H11") (pin "V2") (pinfunction "MOUNT_V2") (pintype "passive"))
      (node (ref "H11") (pin "V3") (pinfunction "MOUNT_V3") (pintype "passive"))
      (node (ref "H11") (pin "V4") (pinfunction "MOUNT_V4") (pintype "passive"))
      (node (ref "H11") (pin "V5") (pinfunction "MOUNT_V5") (pintype "passive"))
      (node (ref "H11") (pin "V6") (pinfunction "MOUNT_V6") (pintype "passive"))
      (node (ref "H11") (pin "V7") (pinfunction "MOUNT_V7") (pintype "passive"))
      (node (ref "H11") (pin "V8") (pinfunction "MOUNT_V8") (pintype "passive"))
      (node (ref "H11") (pin "V9") (pinfunction "MOUNT_V9") (pintype "passive"))
      (node (ref "H12") (pin "1") (pinfunction "MOUNT_1") (pintype "passive"))
      (node (ref "H12") (pin "V1") (pinfunction "MOUNT_V1") (pintype "passive"))
      (node (ref "H12") (pin "V10") (pinfunction "MOUNT_V10") (pintype "passive"))
      (node (ref "H12") (pin "V2") (pinfunction "MOUNT_V2") (pintype "passive"))
      (node (ref "H12") (pin "V3") (pinfunction "MOUNT_V3") (pintype "passive"))
      (node (ref "H12") (pin "V4") (pinfunction "MOUNT_V4") (pintype "passive"))
      (node (ref "H12") (pin "V5") (pinfunction "MOUNT_V5") (pintype "passive"))
      (node (ref "H12") (pin "V6") (pinfunction "MOUNT_V6") (pintype "passive"))
      (node (ref "H12") (pin "V7") (pinfunction "MOUNT_V7") (pintype "passive"))
      (node (ref "H12") (pin "V8") (pinfunction "MOUNT_V8") (pintype "passive"))
      (node (ref "H12") (pin "V9") (pinfunction "MOUNT_V9") (pintype "passive"))
      (node (ref "H2") (pin "1") (pinfunction "MOUNT_1") (pintype "passive"))
      (node (ref "H2") (pin "V1") (pinfunction "MOUNT_V1") (pintype "passive"))
      (node (ref "H2") (pin "V10") (pinfunction "MOUNT_V10") (pintype "passive"))
      (node (ref "H2") (pin "V2") (pinfunction "MOUNT_V2") (pintype "passive"))
      (node (ref "H2") (pin "V3") (pinfunction "MOUNT_V3") (pintype "passive"))
      (node (ref "H2") (pin "V4") (pinfunction "MOUNT_V4") (pintype "passive"))
      (node (ref "H2") (pin "V5") (pinfunction "MOUNT_V5") (pintype "passive"))
      (node (ref "H2") (pin "V6") (pinfunction "MOUNT_V6") (pintype "passive"))
      (node (ref "H2") (pin "V7") (pinfunction "MOUNT_V7") (pintype "passive"))
      (node (ref "H2") (pin "V8") (pinfunction "MOUNT_V8") (pintype "passive"))
      (node (ref "H2") (pin "V9") (pinfunction "MOUNT_V9") (pintype "passive"))
      (node (ref "H6") (pin "1") (pinfunction "MOUNT_1") (pintype "passive"))
      (node (ref "H6") (pin "V1") (pinfunction "MOUNT_V1") (pintype "passive"))
      (node (ref "H6") (pin "V10") (pinfunction "MOUNT_V10") (pintype "passive"))
      (node (ref "H6") (pin "V2") (pinfunction "MOUNT_V2") (pintype "passive"))
      (node (ref "H6") (pin "V3") (pinfunction "MOUNT_V3") (pintype "passive"))
      (node (ref "H6") (pin "V4") (pinfunction "MOUNT_V4") (pintype "passive"))
      (node (ref "H6") (pin "V5") (pinfunction "MOUNT_V5") (pintype "passive"))
      (node (ref "H6") (pin "V6") (pinfunction "MOUNT_V6") (pintype "passive"))
      (node (ref "H6") (pin "V7") (pinfunction "MOUNT_V7") (pintype "passive"))
      (node (ref "H6") (pin "V8") (pinfunction "MOUNT_V8") (pintype "passive"))
      (node (ref "H6") (pin "V9") (pinfunction "MOUNT_V9") (pintype "passive"))
      (node (ref "H7") (pin "1") (pinfunction "MOUNT_1") (pintype "passive"))
      (node (ref "H7") (pin "V1") (pinfunction "MOUNT_V1") (pintype "passive"))
      (node (ref "H7") (pin "V10") (pinfunction "MOUNT_V10") (pintype "passive"))
      (node (ref "H7") (pin "V2") (pinfunction "MOUNT_V2") (pintype "passive"))
      (node (ref "H7") (pin "V3") (pinfunction "MOUNT_V3") (pintype "passive"))
      (node (ref "H7") (pin "V4") (pinfunction "MOUNT_V4") (pintype "passive"))
      (node (ref "H7") (pin "V5") (pinfunction "MOUNT_V5") (pintype "passive"))
      (node (ref "H7") (pin "V6") (pinfunction "MOUNT_V6") (pintype "passive"))
      (node (ref "H7") (pin "V7") (pinfunction "MOUNT_V7") (pintype "passive"))
      (node (ref "H7") (pin "V8") (pinfunction "MOUNT_V8") (pintype "passive"))
      (node (ref "H7") (pin "V9") (pinfunction "MOUNT_V9") (pintype "passive"))
      (node (ref "R1") (pin "2") (pinfunction "2_2") (pintype "passive"))
      (node (ref "R11") (pin "2") (pinfunction "2_2") (pintype "passive"))
      (node (ref "R12") (pin "2") (pinfunction "2_2") (pintype "passive"))
      (node (ref "R13") (pin "2") (pinfunction "2_2") (pintype "passive"))
      (node (ref "R14") (pin "2") (pinfunction "2_2") (pintype "passive"))
      (node (ref "R15") (pin "2") (pinfunction "2_2") (pintype "passive"))
    )
    (net (code "6") (name "DGND") (class "Default")
      (node (ref "C5") (pin "2") (pinfunction "2_2") (pintype "passive"))
      (node (ref "J4") (pin "4") (pinfunction "4_4") (pintype "passive"))
      (node (ref "R10") (pin "2") (pinfunction "2_2") (pintype "passive"))
      (node (ref "R4") (pin "1") (pinfunction "1_1") (pintype "passive"))
      (node (ref "R5") (pin "1") (pinfunction "1_1") (pintype "passive"))
      (node (ref "U1") (pin "9") (pinfunction "DGND_9") (pintype "power_in"))
      (node (ref "U1") (pin "PAD") (pinfunction "DGND_PAD") (pintype "power_in"))
    )
    (net (code "7") (name "I2C_SCL_ADCS") (class "Default")
      (node (ref "J4") (pin "2") (pinfunction "2_2") (pintype "passive"))
      (node (ref "R16") (pin "1") (pinfunction "1_1") (pintype "passive"))
      (node (ref "U1") (pin "15") (pinfunction "SCL_15") (pintype "input"))
    )
    (net (code "8") (name "I2C_SDA_ADCS") (class "Default")
      (node (ref "J4") (pin "1") (pinfunction "1_1") (pintype "passive"))
      (node (ref "R17") (pin "1") (pinfunction "1_1") (pintype "passive"))
      (node (ref "U1") (pin "14") (pinfunction "SDA_14") (pintype "bidirectional"))
    )
    (net (code "9") (name "Net-(AE1-PadCENTER)") (class "Default")
      (node (ref "AE1") (pin "CENTER") (pinfunction "CENTER_CENTER") (pintype "bidirectional"))
      (node (ref "J2") (pin "CENTER") (pinfunction "CENTER_CENTER") (pintype "bidirectional"))
    )
    (net (code "10") (name "Net-(H3-MOUNT-Pad1)") (class "Default")
      (node (ref "H3") (pin "1") (pinfunction "MOUNT_1") (pintype "passive"))
      (node (ref "H3") (pin "V1") (pinfunction "MOUNT_V1") (pintype "passive"))
      (node (ref "H3") (pin "V2") (pinfunction "MOUNT_V2") (pintype "passive"))
      (node (ref "H3") (pin "V3") (pinfunction "MOUNT_V3") (pintype "passive"))
      (node (ref "H3") (pin "V4") (pinfunction "MOUNT_V4") (pintype "passive"))
      (node (ref "H3") (pin "V5") (pinfunction "MOUNT_V5") (pintype "passive"))
      (node (ref "H3") (pin "V6") (pinfunction "MOUNT_V6") (pintype "passive"))
      (node (ref "H3") (pin "V7") (pinfunction "MOUNT_V7") (pintype "passive"))
      (node (ref "H3") (pin "V8") (pinfunction "MOUNT_V8") (pintype "passive"))
      (node (ref "H8") (pin "1") (pinfunction "MOUNT_1") (pintype "passive"))
      (node (ref "H8") (pin "V1") (pinfunction "MOUNT_V1") (pintype "passive"))
      (node (ref "H8") (pin "V2") (pinfunction "MOUNT_V2") (pintype "passive"))
      (node (ref "H8") (pin "V3") (pinfunction "MOUNT_V3") (pintype "passive"))
      (node (ref "H8") (pin "V4") (pinfunction "MOUNT_V4") (pintype "passive"))
      (node (ref "H8") (pin "V5") (pinfunction "MOUNT_V5") (pintype "passive"))
      (node (ref "H8") (pin "V6") (pinfunction "MOUNT_V6") (pintype "passive"))
      (node (ref "H8") (pin "V7") (pinfunction "MOUNT_V7") (pintype "passive"))
      (node (ref "H8") (pin "V8") (pinfunction "MOUNT_V8") (pintype "passive"))
      (node (ref "J1") (pin "3") (pinfunction "3_3") (pintype "passive"))
    )
    (net (code "11") (name "Net-(J1-Pad1)") (class "Default")
      (node (ref "J1") (pin "1") (pinfunction "1_1") (pintype "passive"))
      (node (ref "J1") (pin "2") (pinfunction "2_2") (pintype "passive"))
      (node (ref "R8") (pin "2") (pinfunction "2_2") (pintype "passive"))
      (node (ref "R9") (pin "2") (pinfunction "2_2") (pintype "passive"))
    )
    (net (code "12") (name "Net-(U1-AS0)") (class "Default")
      (node (ref "R2") (pin "1") (pinfunction "1_1") (pintype "passive"))
      (node (ref "R4") (pin "2") (pinfunction "2_2") (pintype "passive"))
      (node (ref "U1") (pin "11") (pinfunction "AS0_11") (pintype "passive"))
    )
    (net (code "13") (name "Net-(U1-AS1)") (class "Default")
      (node (ref "R3") (pin "1") (pinfunction "1_1") (pintype "passive"))
      (node (ref "R5") (pin "2") (pinfunction "2_2") (pintype "passive"))
      (node (ref "U1") (pin "13") (pinfunction "AS1_13") (pintype "passive"))
    )
    (net (code "14") (name "Net-(U1-DCAP)") (class "Default")
      (node (ref "C2") (pin "1") (pinfunction "1_1") (pintype "passive"))
      (node (ref "U1") (pin "8") (pinfunction "DCAP_8") (pintype "passive"))
    )
    (net (code "15") (name "Net-(U1-VREF)") (class "Default")
      (node (ref "C3") (pin "1") (pinfunction "1_1") (pintype "passive"))
      (node (ref "TP1") (pin "1") (pinfunction "1_1") (pintype "passive"))
      (node (ref "U1") (pin "7") (pinfunction "VREF_7") (pintype "bidirectional"))
      (node (ref "U2") (pin "3") (pinfunction "IN+_3") (pintype "passive"))
    )
    (net (code "16") (name "Net-(U1-~{PD}{slash}~{RST})") (class "Default")
      (node (ref "R6") (pin "1") (pinfunction "1_1") (pintype "passive"))
      (node (ref "U1") (pin "17") (pinfunction "~{PD}/~{RST}_17") (pintype "input"))
    )
    (net (code "17") (name "Net-(Z1-PRIMARY)") (class "Default")
      (node (ref "J6") (pin "1") (pinfunction "1_1") (pintype "passive"))
      (node (ref "Z1") (pin "3") (pinfunction "PRIMARY_3") (pintype "passive"))
    )
    (net (code "18") (name "Net-(Z1-PRIMARY-DOT)") (class "Default")
      (node (ref "J5") (pin "1") (pinfunction "1_1") (pintype "passive"))
      (node (ref "Z1") (pin "1") (pinfunction "PRIMARY-DOT_1") (pintype "passive"))
    )
    (net (code "19") (name "Net-(Z1-SECONDARY-DOT)") (class "Default")
      (node (ref "J3") (pin "CENTER") (pinfunction "CENTER_CENTER") (pintype "bidirectional"))
      (node (ref "Z1") (pin "6") (pinfunction "SECONDARY-DOT_6") (pintype "passive"))
    )
    (net (code "20") (name "PGND") (class "Default")
      (node (ref "C10") (pin "2") (pinfunction "2_2") (pintype "passive"))
      (node (ref "C11") (pin "2") (pinfunction "2_2") (pintype "passive"))
      (node (ref "C12") (pin "2") (pinfunction "2_2") (pintype "passive"))
      (node (ref "C13") (pin "2") (pinfunction "2_2") (pintype "passive"))
      (node (ref "C4") (pin "2") (pinfunction "2_2") (pintype "passive"))
      (node (ref "C9") (pin "2") (pinfunction "2_2") (pintype "passive"))
      (node (ref "H4") (pin "1") (pinfunction "MOUNT_1") (pintype "passive"))
      (node (ref "H4") (pin "V1") (pinfunction "MOUNT_V1") (pintype "passive"))
      (node (ref "H4") (pin "V2") (pinfunction "MOUNT_V2") (pintype "passive"))
      (node (ref "H4") (pin "V3") (pinfunction "MOUNT_V3") (pintype "passive"))
      (node (ref "H4") (pin "V4") (pinfunction "MOUNT_V4") (pintype "passive"))
      (node (ref "H4") (pin "V5") (pinfunction "MOUNT_V5") (pintype "passive"))
      (node (ref "H4") (pin "V6") (pinfunction "MOUNT_V6") (pintype "passive"))
      (node (ref "H4") (pin "V7") (pinfunction "MOUNT_V7") (pintype "passive"))
      (node (ref "H4") (pin "V8") (pinfunction "MOUNT_V8") (pintype "passive"))
      (node (ref "H5") (pin "1") (pinfunction "MOUNT_1") (pintype "passive"))
      (node (ref "H5") (pin "V1") (pinfunction "MOUNT_V1") (pintype "passive"))
      (node (ref "H5") (pin "V2") (pinfunction "MOUNT_V2") (pintype "passive"))
      (node (ref "H5") (pin "V3") (pinfunction "MOUNT_V3") (pintype "passive"))
      (node (ref "H5") (pin "V4") (pinfunction "MOUNT_V4") (pintype "passive"))
      (node (ref "H5") (pin "V5") (pinfunction "MOUNT_V5") (pintype "passive"))
      (node (ref "H5") (pin "V6") (pinfunction "MOUNT_V6") (pintype "passive"))
      (node (ref "H5") (pin "V7") (pinfunction "MOUNT_V7") (pintype "passive"))
      (node (ref "H5") (pin "V8") (pinfunction "MOUNT_V8") (pintype "passive"))
      (node (ref "J1") (pin "4") (pinfunction "4_4") (pintype "passive"))
      (node (ref "R1") (pin "1") (pinfunction "1_1") (pintype "passive"))
      (node (ref "R11") (pin "1") (pinfunction "1_1") (pintype "passive"))
      (node (ref "R12") (pin "1") (pinfunction "1_1") (pintype "passive"))
      (node (ref "R13") (pin "1") (pinfunction "1_1") (pintype "passive"))
      (node (ref "R14") (pin "1") (pinfunction "1_1") (pintype "passive"))
      (node (ref "R15") (pin "1") (pinfunction "1_1") (pintype "passive"))
      (node (ref "R8") (pin "1") (pinfunction "1_1") (pintype "passive"))
      (node (ref "R9") (pin "1") (pinfunction "1_1") (pintype "passive"))
    )
    (net (code "21") (name "PHOTO") (class "Default")
      (node (ref "D1") (pin "A") (pinfunction "A_A") (pintype "passive"))
      (node (ref "R7") (pin "2") (pinfunction "2_2") (pintype "passive"))
      (node (ref "U1") (pin "18") (pinfunction "IN0_18") (pintype "input"))
    )
    (net (code "22") (name "RFGND-0") (class "Default")
      (node (ref "H10") (pin "1") (pinfunction "MOUNT_1") (pintype "passive"))
      (node (ref "H10") (pin "V1") (pinfunction "MOUNT_V1") (pintype "passive"))
      (node (ref "H10") (pin "V2") (pinfunction "MOUNT_V2") (pintype "passive"))
      (node (ref "H10") (pin "V3") (pinfunction "MOUNT_V3") (pintype "passive"))
      (node (ref "H10") (pin "V4") (pinfunction "MOUNT_V4") (pintype "passive"))
      (node (ref "H10") (pin "V5") (pinfunction "MOUNT_V5") (pintype "passive"))
      (node (ref "H10") (pin "V6") (pinfunction "MOUNT_V6") (pintype "passive"))
      (node (ref "H10") (pin "V7") (pinfunction "MOUNT_V7") (pintype "passive"))
      (node (ref "H10") (pin "V8") (pinfunction "MOUNT_V8") (pintype "passive"))
      (node (ref "H9") (pin "1") (pinfunction "MOUNT_1") (pintype "passive"))
      (node (ref "H9") (pin "V1") (pinfunction "MOUNT_V1") (pintype "passive"))
      (node (ref "H9") (pin "V2") (pinfunction "MOUNT_V2") (pintype "passive"))
      (node (ref "H9") (pin "V3") (pinfunction "MOUNT_V3") (pintype "passive"))
      (node (ref "H9") (pin "V4") (pinfunction "MOUNT_V4") (pintype "passive"))
      (node (ref "H9") (pin "V5") (pinfunction "MOUNT_V5") (pintype "passive"))
      (node (ref "H9") (pin "V6") (pinfunction "MOUNT_V6") (pintype "passive"))
      (node (ref "H9") (pin "V7") (pinfunction "MOUNT_V7") (pintype "passive"))
      (node (ref "H9") (pin "V8") (pinfunction "MOUNT_V8") (pintype "passive"))
      (node (ref "J3") (pin "SHIELD@1") (pinfunction "SHIELD_SHIELD@1") (pintype "bidirectional"))
      (node (ref "J3") (pin "SHIELD@13") (pinfunction "SHIELD_SHIELD@13") (pintype "bidirectional"))
      (node (ref "J3") (pin "SHIELD@2") (pinfunction "SHIELD_SHIELD@2") (pintype "bidirectional"))
      (node (ref "Z1") (pin "4") (pinfunction "SECONDARY_4") (pintype "passive"))
    )
    (net (code "23") (name "RFGND-1") (class "Default")
      (node (ref "AE1") (pin "GND") (pinfunction "SHIELD_GND") (pintype "bidirectional"))
      (node (ref "J2") (pin "SHIELD@1") (pinfunction "SHIELD_SHIELD@1") (pintype "bidirectional"))
      (node (ref "J2") (pin "SHIELD@13") (pinfunction "SHIELD_SHIELD@13") (pintype "bidirectional"))
      (node (ref "J2") (pin "SHIELD@2") (pinfunction "SHIELD_SHIELD@2") (pintype "bidirectional"))
    )
    (net (code "24") (name "THERM-0") (class "Default")
      (node (ref "RN1") (pin "6") (pinfunction "5_6") (pintype "passive"))
      (node (ref "RT3") (pin "2") (pinfunction "2_2") (pintype "passive"))
      (node (ref "U1") (pin "19") (pinfunction "IN1_19") (pintype "input"))
    )
    (net (code "25") (name "THERM-1") (class "Default")
      (node (ref "RN1") (pin "7") (pinfunction "6_7") (pintype "passive"))
      (node (ref "RT4") (pin "2") (pinfunction "2_2") (pintype "passive"))
      (node (ref "U1") (pin "20") (pinfunction "IN2_20") (pintype "input"))
    )
    (net (code "26") (name "THERM-2") (class "Default")
      (node (ref "RN1") (pin "8") (pinfunction "7_8") (pintype "passive"))
      (node (ref "RT7") (pin "2") (pinfunction "2_2") (pintype "passive"))
      (node (ref "U1") (pin "1") (pinfunction "IN3_1") (pintype "input"))
    )
    (net (code "27") (name "THERM-3") (class "Default")
      (node (ref "RN1") (pin "4") (pinfunction "4_4") (pintype "passive"))
      (node (ref "RT6") (pin "2") (pinfunction "2_2") (pintype "passive"))
      (node (ref "U1") (pin "2") (pinfunction "IN4_2") (pintype "input"))
    )
    (net (code "28") (name "THERM-4") (class "Default")
      (node (ref "RN1") (pin "3") (pinfunction "3_3") (pintype "passive"))
      (node (ref "RT1") (pin "2") (pinfunction "2_2") (pintype "passive"))
      (node (ref "U1") (pin "3") (pinfunction "IN5_3") (pintype "input"))
    )
    (net (code "29") (name "THERM-5") (class "Default")
      (node (ref "RN1") (pin "2") (pinfunction "2_2") (pintype "passive"))
      (node (ref "RT5") (pin "2") (pinfunction "2_2") (pintype "passive"))
      (node (ref "U1") (pin "4") (pinfunction "IN6_4") (pintype "input"))
    )
    (net (code "30") (name "THERM-6") (class "Default")
      (node (ref "RN1") (pin "1") (pinfunction "1_1") (pintype "passive"))
      (node (ref "RT2") (pin "2") (pinfunction "2_2") (pintype "passive"))
      (node (ref "U1") (pin "5") (pinfunction "IN7_5") (pintype "input"))
    )
    (net (code "31") (name "unconnected-(RN1-8-Pad9)") (class "Default")
      (node (ref "RN1") (pin "9") (pinfunction "8_9") (pintype "passive"))
    )
    (net (code "32") (name "unconnected-(U1-ALERT-Pad12)") (class "Default")
      (node (ref "U1") (pin "12") (pinfunction "ALERT_12") (pintype "output"))
    )
  )
)
